# ProProject___2024-07-08.net
KiCad netlist of a schematic drawn in EasyEDA Pro
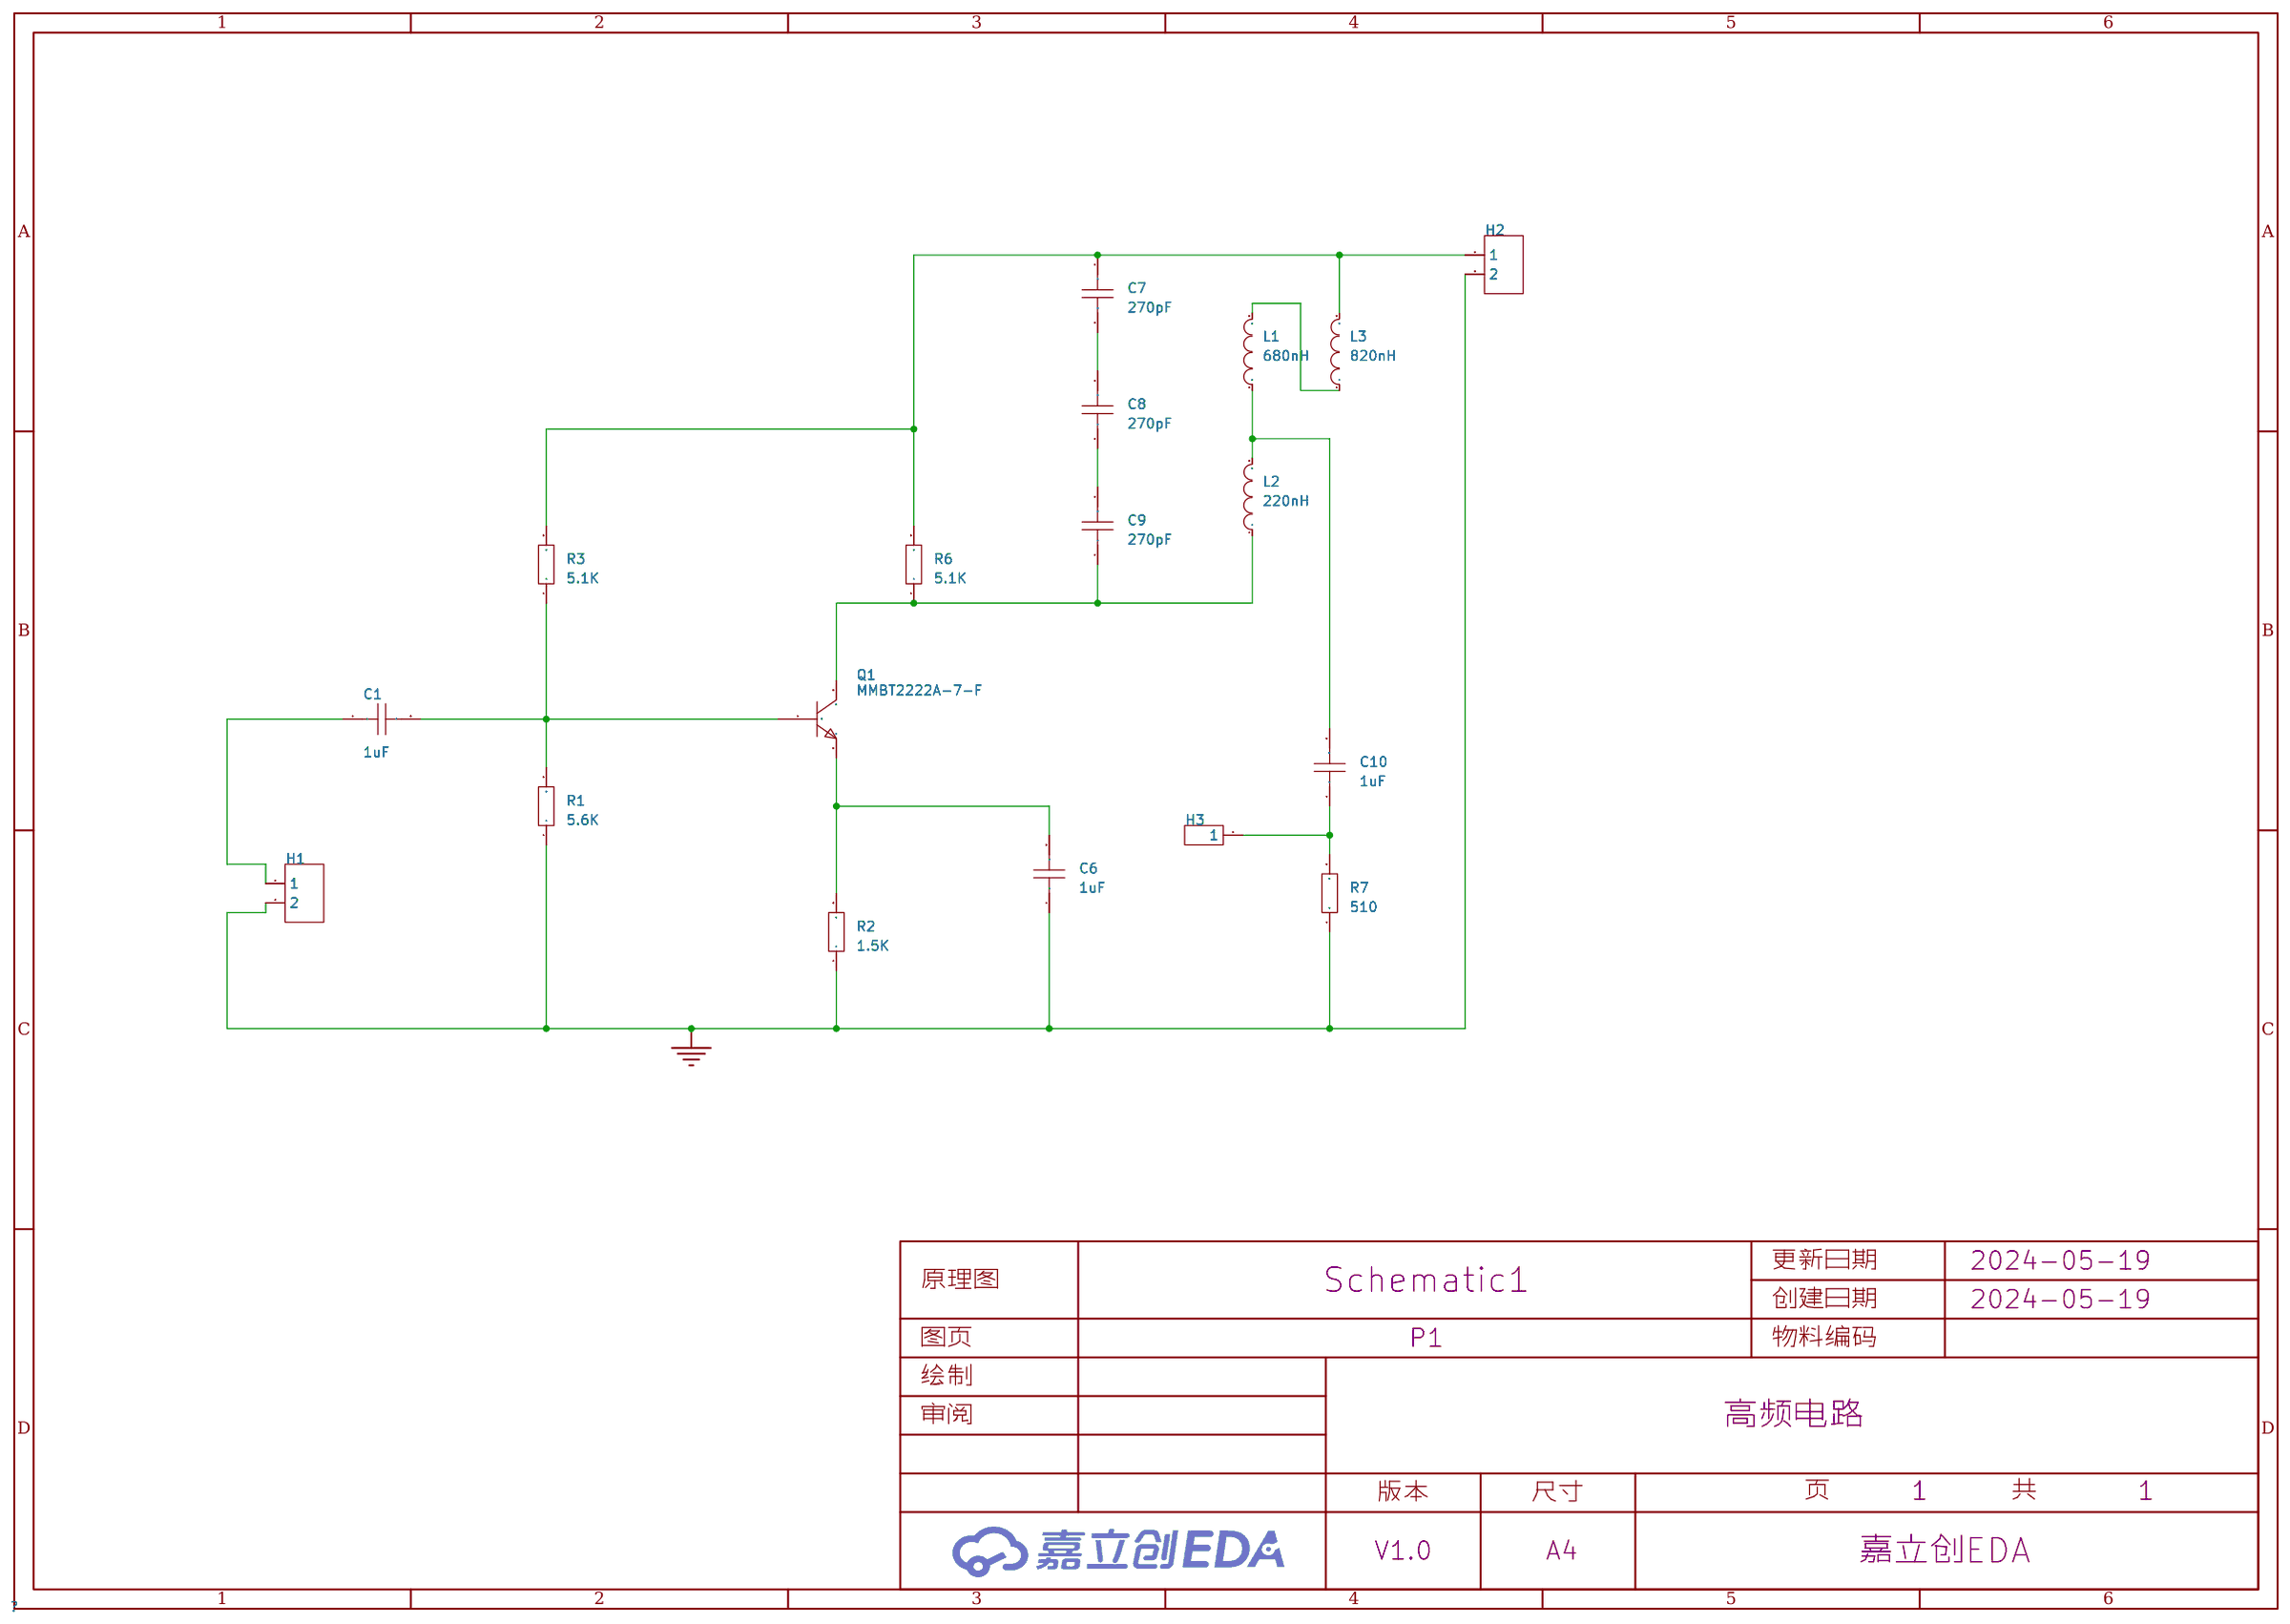
[diagram p0: schematic sheet]

(export (version "E")
  (design (tool "Eeschema 10.0.6"))
  (components
    (comp (ref "C1")
      (value "1uF")
      (footprint "easyedapro:C0805")
      (libsource (lib "easyedapro") (part "CapAcitance"))
    )
    (comp (ref "C6")
      (value "1uF")
      (footprint "easyedapro:C0805")
      (libsource (lib "easyedapro") (part "CapAcitance"))
    )
    (comp (ref "C7")
      (value "270pF")
      (footprint "easyedapro:C0805")
      (libsource (lib "easyedapro") (part "CapAcitance"))
    )
    (comp (ref "C8")
      (value "270pF")
      (footprint "easyedapro:C0805")
      (libsource (lib "easyedapro") (part "CapAcitance"))
    )
    (comp (ref "C9")
      (value "270pF")
      (footprint "easyedapro:C0805")
      (libsource (lib "easyedapro") (part "CapAcitance"))
    )
    (comp (ref "C10")
      (value "1uF")
      (footprint "easyedapro:C0805")
      (libsource (lib "easyedapro") (part "CapAcitance"))
    )
    (comp (ref "H1")
      (value "~")
      (footprint "easyedapro:HDR-TH_2P-P2.54-V-F")
      (libsource (lib "easyedapro") (part "Header-Female-2.54_1x2"))
    )
    (comp (ref "H2")
      (value "~")
      (footprint "easyedapro:HDR-TH_2P-P2.54-V-F")
      (libsource (lib "easyedapro") (part "Header-Female-2.54_1x2"))
    )
    (comp (ref "H3")
      (value "~")
      (footprint "easyedapro:HDR-TH_1P-V-M_XKB_X4611WV-01I-C28D40")
      (libsource (lib "easyedapro") (part "HDR_1x1"))
    )
    (comp (ref "L1")
      (value "680nH")
      (footprint "easyedapro:L0805")
      (libsource (lib "easyedapro") (part "SDFL2012S100KTF"))
    )
    (comp (ref "L2")
      (value "220nH")
      (footprint "easyedapro:L0805")
      (libsource (lib "easyedapro") (part "SDFL2012S100KTF"))
    )
    (comp (ref "L3")
      (value "820nH")
      (footprint "easyedapro:L0805")
      (libsource (lib "easyedapro") (part "SDFL2012S100KTF"))
    )
    (comp (ref "Q1")
      (value "MMBT2222A-7-F")
      (footprint "easyedapro:SOT-23-3_L2.9-W1.6-P1.90-LS2.8-BR")
      (description "晶体管类型:NPN;集电极电流(Ic):600mA;集射极击穿电压(Vceo):40V;功率(Pd):310mW;直流电流增益(hFE@Ic,Vce):100@150mA,10V;")
      (fields (field (name "Manufacturer") "DIODES(美台)"))
      (libsource (lib "easyedapro") (part "MMBT2222A-7-F"))
    )
    (comp (ref "R1") (value "5.6K") (footprint "easyedapro:R0603") (libsource (lib "easyedapro") (part "电阻")))
    (comp (ref "R2") (value "1.5K") (footprint "easyedapro:R0603") (libsource (lib "easyedapro") (part "电阻")))
    (comp (ref "R3") (value "5.1K") (footprint "easyedapro:R0603") (libsource (lib "easyedapro") (part "电阻")))
    (comp (ref "R6") (value "5.1K") (footprint "easyedapro:R0603") (libsource (lib "easyedapro") (part "电阻")))
    (comp (ref "R7") (value "510") (footprint "easyedapro:R0603") (libsource (lib "easyedapro") (part "电阻")))
  )
  (nets
    (net (code "1") (name "GND") (class "Default")
      (node (ref "C6") (pin "1") (pinfunction "1_1") (pintype "input"))
      (node (ref "H1") (pin "2") (pinfunction "2_2") (pintype "input"))
      (node (ref "H2") (pin "2") (pinfunction "2_2") (pintype "input"))
      (node (ref "R1") (pin "1") (pinfunction "1_1") (pintype "input"))
      (node (ref "R2") (pin "1") (pinfunction "1_1") (pintype "input"))
      (node (ref "R7") (pin "1") (pinfunction "1_1") (pintype "input"))
    )
    (net (code "2") (name "Net-(C1-Pad1)") (class "Default")
      (node (ref "C1") (pin "1") (pinfunction "1_1") (pintype "input"))
      (node (ref "H1") (pin "1") (pinfunction "1_1") (pintype "input"))
    )
    (net (code "3") (name "Net-(C7-Pad1)") (class "Default")
      (node (ref "C7") (pin "1") (pinfunction "1_1") (pintype "input"))
      (node (ref "H2") (pin "1") (pinfunction "1_1") (pintype "input"))
      (node (ref "L3") (pin "2") (pinfunction "2_2") (pintype "input"))
      (node (ref "R3") (pin "2") (pinfunction "2_2") (pintype "input"))
      (node (ref "R6") (pin "2") (pinfunction "2_2") (pintype "input"))
    )
    (net (code "4") (name "Net-(C7-Pad2)") (class "Default")
      (node (ref "C7") (pin "2") (pinfunction "2_2") (pintype "input"))
      (node (ref "C8") (pin "2") (pinfunction "2_2") (pintype "input"))
    )
    (net (code "5") (name "Net-(C8-Pad1)") (class "Default")
      (node (ref "C8") (pin "1") (pinfunction "1_1") (pintype "input"))
      (node (ref "C9") (pin "2") (pinfunction "2_2") (pintype "input"))
    )
    (net (code "6") (name "Net-(C10-Pad1)") (class "Default")
      (node (ref "C10") (pin "1") (pinfunction "1_1") (pintype "input"))
      (node (ref "H3") (pin "1") (pinfunction "1_1") (pintype "unspecified"))
      (node (ref "R7") (pin "2") (pinfunction "2_2") (pintype "input"))
    )
    (net (code "7") (name "Net-(C10-Pad2)") (class "Default")
      (node (ref "C10") (pin "2") (pinfunction "2_2") (pintype "input"))
      (node (ref "L1") (pin "1") (pinfunction "1_1") (pintype "input"))
      (node (ref "L2") (pin "2") (pinfunction "2_2") (pintype "input"))
    )
    (net (code "8") (name "Net-(L1-Pad2)") (class "Default")
      (node (ref "L1") (pin "2") (pinfunction "2_2") (pintype "input"))
      (node (ref "L3") (pin "1") (pinfunction "1_1") (pintype "input"))
    )
    (net (code "9") (name "Net-(Q1-B)") (class "Default")
      (node (ref "C1") (pin "2") (pinfunction "2_2") (pintype "input"))
      (node (ref "Q1") (pin "1") (pinfunction "B_1") (pintype "unspecified"))
      (node (ref "R1") (pin "2") (pinfunction "2_2") (pintype "input"))
      (node (ref "R3") (pin "1") (pinfunction "1_1") (pintype "input"))
    )
    (net (code "10") (name "Net-(Q1-C)") (class "Default")
      (node (ref "C9") (pin "1") (pinfunction "1_1") (pintype "input"))
      (node (ref "L2") (pin "1") (pinfunction "1_1") (pintype "input"))
      (node (ref "Q1") (pin "3") (pinfunction "C_3") (pintype "unspecified"))
      (node (ref "R6") (pin "1") (pinfunction "1_1") (pintype "input"))
    )
    (net (code "11") (name "Net-(Q1-E)") (class "Default")
      (node (ref "C6") (pin "2") (pinfunction "2_2") (pintype "input"))
      (node (ref "Q1") (pin "2") (pinfunction "E_2") (pintype "unspecified"))
      (node (ref "R2") (pin "2") (pinfunction "2_2") (pintype "input"))
    )
  )
)
